# CPLD.net
KiCad netlist of a schematic drawn in Altium Designer
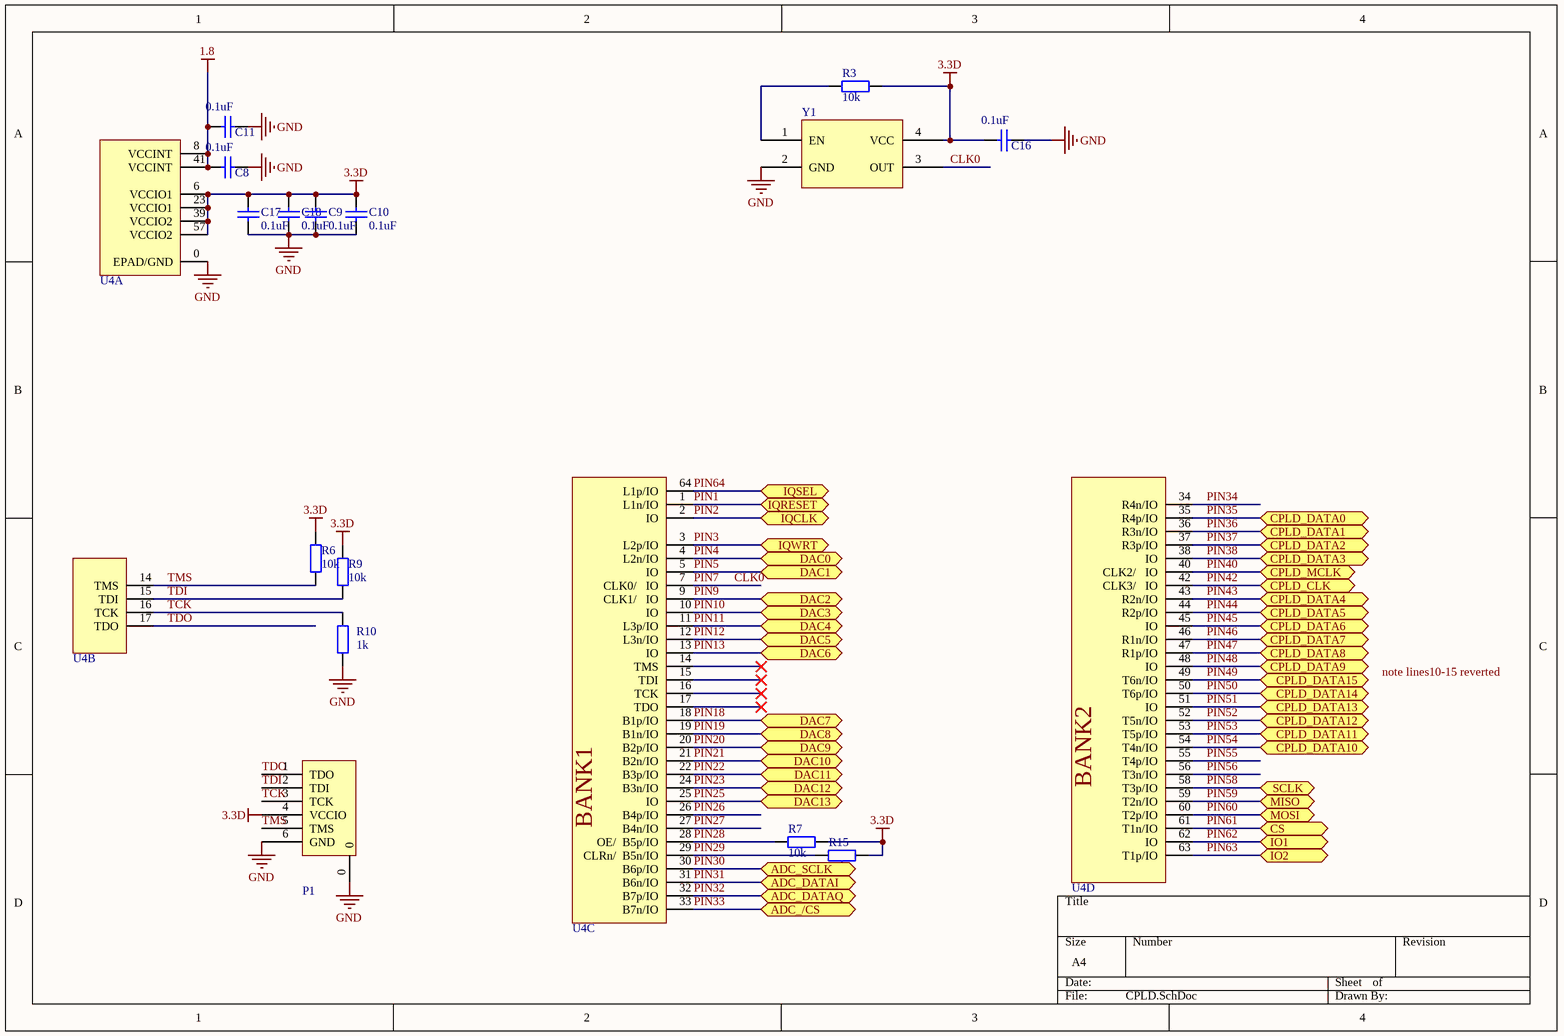
[diagram p0: CPLD.SchDoc]

(export (version "E")
  (design (tool "Eeschema 10.0.6"))
  (components
    (comp (ref "C8")
      (value "0.1uF")
      (footprint "0402")
      (description "Capacitor")
      (fields (field (name "PUBLISHER") "Altium Limited"))
      (libsource (lib "RTC6705") (part "Cap"))
    )
    (comp (ref "C9")
      (value "0.1uF")
      (footprint "0402")
      (description "Capacitor")
      (fields (field (name "PUBLISHER") "Altium Limited"))
      (libsource (lib "RTC6705") (part "Cap"))
    )
    (comp (ref "C10")
      (value "0.1uF")
      (footprint "0402")
      (description "Capacitor")
      (fields (field (name "PUBLISHER") "Altium Limited"))
      (libsource (lib "RTC6705") (part "Cap"))
    )
    (comp (ref "C11")
      (value "0.1uF")
      (footprint "0402")
      (description "Capacitor")
      (fields (field (name "PUBLISHER") "Altium Limited"))
      (libsource (lib "RTC6705") (part "Cap"))
    )
    (comp (ref "C16")
      (value "0.1uF")
      (footprint "0402")
      (description "Capacitor")
      (fields (field (name "PUBLISHER") "Altium Limited"))
      (libsource (lib "RTC6705") (part "Cap"))
    )
    (comp (ref "C17")
      (value "0.1uF")
      (footprint "0402")
      (description "Capacitor")
      (fields (field (name "PUBLISHER") "Altium Limited"))
      (libsource (lib "RTC6705") (part "Cap"))
    )
    (comp (ref "C18")
      (value "0.1uF")
      (footprint "0402")
      (description "Capacitor")
      (fields (field (name "PUBLISHER") "Altium Limited"))
      (libsource (lib "RTC6705") (part "Cap"))
    )
    (comp (ref "P1") (value "JTAG-6P") (footprint "GH1.25-6") (libsource (lib "sch") (part "JTAG-6P")))
    (comp (ref "R3")
      (value "10k")
      (footprint "0402")
      (description "Resistor")
      (fields (field (name "PUBLISHER") "Altium Limited"))
      (libsource (lib "") (part "Res2_1"))
    )
    (comp (ref "R6")
      (value "10k")
      (footprint "0402")
      (description "Resistor")
      (fields (field (name "PUBLISHER") "Altium Limited"))
      (libsource (lib "RTC6705") (part "Res2"))
    )
    (comp (ref "R7")
      (value "10k")
      (footprint "0402")
      (description "Resistor")
      (fields (field (name "PUBLISHER") "Altium Limited"))
      (libsource (lib "") (part "Res2_1"))
    )
    (comp (ref "R9")
      (value "10k")
      (footprint "0402")
      (description "Resistor")
      (fields (field (name "PUBLISHER") "Altium Limited"))
      (libsource (lib "RTC6705") (part "Res2"))
    )
    (comp (ref "R10")
      (value "1k")
      (footprint "0402")
      (description "Resistor")
      (fields (field (name "PUBLISHER") "Altium Limited"))
      (libsource (lib "RTC6705") (part "Res2"))
    )
    (comp (ref "R15")
      (value "10k")
      (footprint "0402")
      (description "Resistor")
      (fields (field (name "PUBLISHER") "Altium Limited"))
      (libsource (lib "") (part "Res2_1"))
    )
    (comp (ref "U4")
      (value "5M160ZE64")
      (footprint "5M160ZE64")
      (libsource (lib "5M160ZE64") (part "5M160ZE64"))
    )
    (comp (ref "Y1") (value "OSC_50M") (footprint "TXC_7Q") (libsource (lib "F4SDR") (part "OSC_50M")))
  )
  (nets
    (net (code "1") (name "/CLK0") (class "Default")
      (node (ref "U4") (pin "7") (pinfunction "CLK0/___IO_7") (pintype "passive"))
      (node (ref "Y1") (pin "3") (pinfunction "OUT_3") (pintype "passive"))
    )
    (net (code "2") (name "/PIN1") (class "Default")
      (node (ref "U4") (pin "1") (pinfunction "L1n/IO_1") (pintype "passive"))
    )
    (net (code "3") (name "/PIN2") (class "Default")
      (node (ref "U4") (pin "2") (pinfunction "IO_2") (pintype "passive"))
    )
    (net (code "4") (name "/PIN3") (class "Default")
      (node (ref "U4") (pin "3") (pinfunction "L2p/IO_3") (pintype "passive"))
    )
    (net (code "5") (name "/PIN4") (class "Default")
      (node (ref "U4") (pin "4") (pinfunction "L2n/IO_4") (pintype "passive"))
    )
    (net (code "6") (name "/PIN5") (class "Default")
      (node (ref "U4") (pin "5") (pinfunction "IO_5") (pintype "passive"))
    )
    (net (code "7") (name "/PIN9") (class "Default")
      (node (ref "U4") (pin "9") (pinfunction "CLK1/___IO_9") (pintype "passive"))
    )
    (net (code "8") (name "/PIN10") (class "Default")
      (node (ref "U4") (pin "10") (pinfunction "IO_10") (pintype "passive"))
    )
    (net (code "9") (name "/PIN11") (class "Default")
      (node (ref "U4") (pin "11") (pinfunction "L3p/IO_11") (pintype "passive"))
    )
    (net (code "10") (name "/PIN12") (class "Default")
      (node (ref "U4") (pin "12") (pinfunction "L3n/IO_12") (pintype "passive"))
    )
    (net (code "11") (name "/PIN13") (class "Default")
      (node (ref "U4") (pin "13") (pinfunction "IO_13") (pintype "passive"))
    )
    (net (code "12") (name "/PIN18") (class "Default")
      (node (ref "U4") (pin "18") (pinfunction "B1p/IO_18") (pintype "passive"))
    )
    (net (code "13") (name "/PIN19") (class "Default")
      (node (ref "U4") (pin "19") (pinfunction "B1n/IO_19") (pintype "passive"))
    )
    (net (code "14") (name "/PIN20") (class "Default")
      (node (ref "U4") (pin "20") (pinfunction "B2p/IO_20") (pintype "passive"))
    )
    (net (code "15") (name "/PIN21") (class "Default")
      (node (ref "U4") (pin "21") (pinfunction "B2n/IO_21") (pintype "passive"))
    )
    (net (code "16") (name "/PIN22") (class "Default")
      (node (ref "U4") (pin "22") (pinfunction "B3p/IO_22") (pintype "passive"))
    )
    (net (code "17") (name "/PIN23") (class "Default")
      (node (ref "U4") (pin "24") (pinfunction "B3n/IO_24") (pintype "passive"))
    )
    (net (code "18") (name "/PIN25") (class "Default")
      (node (ref "U4") (pin "25") (pinfunction "IO_25") (pintype "passive"))
    )
    (net (code "19") (name "/PIN26") (class "Default")
      (node (ref "U4") (pin "26") (pinfunction "B4p/IO_26") (pintype "passive"))
    )
    (net (code "20") (name "/PIN27") (class "Default")
      (node (ref "U4") (pin "27") (pinfunction "B4n/IO_27") (pintype "passive"))
    )
    (net (code "21") (name "/PIN28") (class "Default")
      (node (ref "R7") (pin "1") (pinfunction "1_1") (pintype "passive"))
      (node (ref "U4") (pin "28") (pinfunction "OE/__B5p/IO_28") (pintype "passive"))
    )
    (net (code "22") (name "/PIN29") (class "Default")
      (node (ref "R15") (pin "1") (pinfunction "1_1") (pintype "passive"))
      (node (ref "U4") (pin "29") (pinfunction "CLRn/__B5n/IO_29") (pintype "passive"))
    )
    (net (code "23") (name "/PIN30") (class "Default")
      (node (ref "U4") (pin "30") (pinfunction "B6p/IO_30") (pintype "passive"))
    )
    (net (code "24") (name "/PIN31") (class "Default")
      (node (ref "U4") (pin "31") (pinfunction "B6n/IO_31") (pintype "passive"))
    )
    (net (code "25") (name "/PIN32") (class "Default")
      (node (ref "U4") (pin "32") (pinfunction "B7p/IO_32") (pintype "passive"))
    )
    (net (code "26") (name "/PIN33") (class "Default")
      (node (ref "U4") (pin "33") (pinfunction "B7n/IO_33") (pintype "passive"))
    )
    (net (code "27") (name "/PIN34") (class "Default")
      (node (ref "U4") (pin "34") (pinfunction "R4n/IO_34") (pintype "passive"))
    )
    (net (code "28") (name "/PIN35") (class "Default")
      (node (ref "U4") (pin "35") (pinfunction "R4p/IO_35") (pintype "passive"))
    )
    (net (code "29") (name "/PIN36") (class "Default")
      (node (ref "U4") (pin "36") (pinfunction "R3n/IO_36") (pintype "passive"))
    )
    (net (code "30") (name "/PIN37") (class "Default")
      (node (ref "U4") (pin "37") (pinfunction "R3p/IO_37") (pintype "passive"))
    )
    (net (code "31") (name "/PIN38") (class "Default")
      (node (ref "U4") (pin "38") (pinfunction "IO_38") (pintype "passive"))
    )
    (net (code "32") (name "/PIN40") (class "Default")
      (node (ref "U4") (pin "40") (pinfunction "CLK2/___IO_40") (pintype "passive"))
    )
    (net (code "33") (name "/PIN42") (class "Default")
      (node (ref "U4") (pin "42") (pinfunction "CLK3/___IO_42") (pintype "passive"))
    )
    (net (code "34") (name "/PIN43") (class "Default")
      (node (ref "U4") (pin "43") (pinfunction "R2n/IO_43") (pintype "passive"))
    )
    (net (code "35") (name "/PIN44") (class "Default")
      (node (ref "U4") (pin "44") (pinfunction "R2p/IO_44") (pintype "passive"))
    )
    (net (code "36") (name "/PIN45") (class "Default")
      (node (ref "U4") (pin "45") (pinfunction "IO_45") (pintype "passive"))
    )
    (net (code "37") (name "/PIN46") (class "Default")
      (node (ref "U4") (pin "46") (pinfunction "R1n/IO_46") (pintype "passive"))
    )
    (net (code "38") (name "/PIN47") (class "Default")
      (node (ref "U4") (pin "47") (pinfunction "R1p/IO_47") (pintype "passive"))
    )
    (net (code "39") (name "/PIN48") (class "Default")
      (node (ref "U4") (pin "48") (pinfunction "IO_48") (pintype "passive"))
    )
    (net (code "40") (name "/PIN49") (class "Default")
      (node (ref "U4") (pin "49") (pinfunction "T6n/IO_49") (pintype "passive"))
    )
    (net (code "41") (name "/PIN50") (class "Default")
      (node (ref "U4") (pin "50") (pinfunction "T6p/IO_50") (pintype "passive"))
    )
    (net (code "42") (name "/PIN51") (class "Default")
      (node (ref "U4") (pin "51") (pinfunction "IO_51") (pintype "passive"))
    )
    (net (code "43") (name "/PIN52") (class "Default")
      (node (ref "U4") (pin "52") (pinfunction "T5n/IO_52") (pintype "passive"))
    )
    (net (code "44") (name "/PIN53") (class "Default")
      (node (ref "U4") (pin "53") (pinfunction "T5p/IO_53") (pintype "passive"))
    )
    (net (code "45") (name "/PIN54") (class "Default")
      (node (ref "U4") (pin "54") (pinfunction "T4n/IO_54") (pintype "passive"))
    )
    (net (code "46") (name "/PIN55") (class "Default")
      (node (ref "U4") (pin "55") (pinfunction "T4p/IO_55") (pintype "passive"))
    )
    (net (code "47") (name "/PIN56") (class "Default")
      (node (ref "U4") (pin "56") (pinfunction "T3n/IO_56") (pintype "passive"))
    )
    (net (code "48") (name "/PIN58") (class "Default")
      (node (ref "U4") (pin "58") (pinfunction "T3p/IO_58") (pintype "passive"))
    )
    (net (code "49") (name "/PIN59") (class "Default")
      (node (ref "U4") (pin "59") (pinfunction "T2n/IO_59") (pintype "passive"))
    )
    (net (code "50") (name "/PIN60") (class "Default")
      (node (ref "U4") (pin "60") (pinfunction "T2p/IO_60") (pintype "passive"))
    )
    (net (code "51") (name "/PIN61") (class "Default")
      (node (ref "U4") (pin "61") (pinfunction "T1n/IO_61") (pintype "passive"))
    )
    (net (code "52") (name "/PIN62") (class "Default")
      (node (ref "U4") (pin "62") (pinfunction "IO_62") (pintype "passive"))
    )
    (net (code "53") (name "/PIN63") (class "Default")
      (node (ref "U4") (pin "63") (pinfunction "T1p/IO_63") (pintype "passive"))
    )
    (net (code "54") (name "/PIN64") (class "Default")
      (node (ref "U4") (pin "64") (pinfunction "L1p/IO_64") (pintype "passive"))
    )
    (net (code "55") (name "/TCK") (class "Default")
      (node (ref "P1") (pin "3") (pinfunction "TCK_3") (pintype "passive"))
      (node (ref "R10") (pin "2") (pinfunction "2_2") (pintype "passive"))
      (node (ref "U4") (pin "16") (pinfunction "TCK_16") (pintype "passive"))
    )
    (net (code "56") (name "/TDI") (class "Default")
      (node (ref "P1") (pin "2") (pinfunction "TDI_2") (pintype "passive"))
      (node (ref "R9") (pin "1") (pinfunction "1_1") (pintype "passive"))
      (node (ref "U4") (pin "15") (pinfunction "TDI_15") (pintype "passive"))
    )
    (net (code "57") (name "/TDO") (class "Default")
      (node (ref "P1") (pin "1") (pinfunction "TDO_1") (pintype "passive"))
      (node (ref "U4") (pin "17") (pinfunction "TDO_17") (pintype "passive"))
    )
    (net (code "58") (name "/TMS") (class "Default")
      (node (ref "P1") (pin "5") (pinfunction "TMS_5") (pintype "passive"))
      (node (ref "R6") (pin "1") (pinfunction "1_1") (pintype "passive"))
      (node (ref "U4") (pin "14") (pinfunction "TMS_14") (pintype "passive"))
    )
    (net (code "60") (name "1.8") (class "Default")
      (node (ref "C11") (pin "2") (pinfunction "2_2") (pintype "passive"))
      (node (ref "C8") (pin "2") (pinfunction "2_2") (pintype "passive"))
      (node (ref "U4") (pin "41") (pinfunction "VCCINT_41") (pintype "passive"))
      (node (ref "U4") (pin "8") (pinfunction "VCCINT_8") (pintype "passive"))
    )
    (net (code "61") (name "3.3D") (class "Default")
      (node (ref "C10") (pin "2") (pinfunction "2_2") (pintype "passive"))
      (node (ref "C16") (pin "2") (pinfunction "2_2") (pintype "passive"))
      (node (ref "C17") (pin "2") (pinfunction "2_2") (pintype "passive"))
      (node (ref "C18") (pin "2") (pinfunction "2_2") (pintype "passive"))
      (node (ref "C9") (pin "2") (pinfunction "2_2") (pintype "passive"))
      (node (ref "P1") (pin "4") (pinfunction "VCCIO_4") (pintype "passive"))
      (node (ref "R15") (pin "2") (pinfunction "2_2") (pintype "passive"))
      (node (ref "R3") (pin "2") (pinfunction "2_2") (pintype "passive"))
      (node (ref "R6") (pin "2") (pinfunction "2_2") (pintype "passive"))
      (node (ref "R7") (pin "2") (pinfunction "2_2") (pintype "passive"))
      (node (ref "R9") (pin "2") (pinfunction "2_2") (pintype "passive"))
      (node (ref "U4") (pin "23") (pinfunction "VCCIO1_23") (pintype "passive"))
      (node (ref "U4") (pin "39") (pinfunction "VCCIO2_39") (pintype "passive"))
      (node (ref "U4") (pin "57") (pinfunction "VCCIO2_57") (pintype "passive"))
      (node (ref "U4") (pin "6") (pinfunction "VCCIO1_6") (pintype "passive"))
      (node (ref "Y1") (pin "4") (pinfunction "VCC_4") (pintype "passive"))
    )
    (net (code "62") (name "GND") (class "Default")
      (node (ref "C10") (pin "1") (pinfunction "1_1") (pintype "passive"))
      (node (ref "C11") (pin "1") (pinfunction "1_1") (pintype "passive"))
      (node (ref "C16") (pin "1") (pinfunction "1_1") (pintype "passive"))
      (node (ref "C17") (pin "1") (pinfunction "1_1") (pintype "passive"))
      (node (ref "C18") (pin "1") (pinfunction "1_1") (pintype "passive"))
      (node (ref "C8") (pin "1") (pinfunction "1_1") (pintype "passive"))
      (node (ref "C9") (pin "1") (pinfunction "1_1") (pintype "passive"))
      (node (ref "P1") (pin "0") (pinfunction "0_0") (pintype "passive"))
      (node (ref "P1") (pin "6") (pinfunction "GND_6") (pintype "passive"))
      (node (ref "R10") (pin "1") (pinfunction "1_1") (pintype "passive"))
      (node (ref "U4") (pin "0") (pinfunction "EPAD/GND_0") (pintype "passive"))
      (node (ref "Y1") (pin "2") (pinfunction "GND_2") (pintype "passive"))
    )
    (net (code "63") (name "Net-(Y1-EN)") (class "Default")
      (node (ref "R3") (pin "1") (pinfunction "1_1") (pintype "passive"))
      (node (ref "Y1") (pin "1") (pinfunction "EN_1") (pintype "passive"))
    )
    (net (code "64") (name "unconnected-(U4C-TCK-Pad16)") (class "Default")
      (node (ref "U4") (pin "16") (pinfunction "TCK_16") (pintype "passive+no_connect"))
    )
    (net (code "65") (name "unconnected-(U4C-TDI-Pad15)") (class "Default")
      (node (ref "U4") (pin "15") (pinfunction "TDI_15") (pintype "passive+no_connect"))
    )
    (net (code "66") (name "unconnected-(U4C-TDO-Pad17)") (class "Default")
      (node (ref "U4") (pin "17") (pinfunction "TDO_17") (pintype "passive+no_connect"))
    )
    (net (code "67") (name "unconnected-(U4C-TMS-Pad14)") (class "Default")
      (node (ref "U4") (pin "14") (pinfunction "TMS_14") (pintype "passive+no_connect"))
    )
  )
)
